# OPID_351_5V_Step-down_regulator_v2.net
KiCad netlist of a schematic drawn in Altium Designer
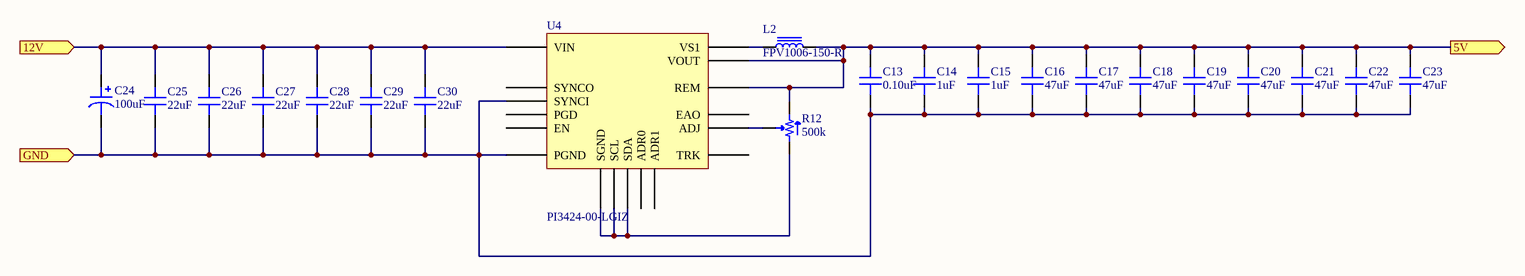
[diagram p0: OPID[351] 5V Step-down regulator v2.SchDoc]

(export (version "E")
  (design (tool "Eeschema 10.0.6"))
  (components
    (comp (ref "C13")
      (value "0.10uF")
      (footprint "CAP 1206/3216 - 1.0MM")
      (description "CAP CER 0.1UF 50V X7R 1206")
      (fields
        (field (name "PART NUMBER") "GRM319R71H104KA01D")
        (field (name "MANUFACTURER") "Murata Electronics North America")
      )
      (libsource (lib "Celestial Library Database") (part "Capacitor"))
    )
    (comp (ref "C14")
      (value "1uF")
      (footprint "CAP 0603/1608")
      (description "CAP CER 1UF 16V X7R 0603")
      (fields
        (field (name "PART NUMBER") "GRM188R71C105KA12D")
        (field (name "MANUFACTURER") "Murata Electronics North America")
      )
      (libsource (lib "Celestial Library Database") (part "Capacitor"))
    )
    (comp (ref "C15")
      (value "1uF")
      (footprint "CAP 0603/1608")
      (description "CAP CER 1UF 16V X7R 0603")
      (fields
        (field (name "PART NUMBER") "GRM188R71C105KA12D")
        (field (name "MANUFACTURER") "Murata Electronics North America")
      )
      (libsource (lib "Celestial Library Database") (part "Capacitor"))
    )
    (comp (ref "C16")
      (value "47uF")
      (footprint "CAP 1206/3216")
      (description "CAP CER 47UF 10V X5R 1206")
      (fields
        (field (name "PART NUMBER") "GRM31CR61A476ME15L")
        (field (name "MANUFACTURER") "Murata Electronics North America")
      )
      (libsource (lib "Celestial Library Database") (part "Capacitor"))
    )
    (comp (ref "C17")
      (value "47uF")
      (footprint "CAP 1206/3216")
      (description "CAP CER 47UF 10V X5R 1206")
      (fields
        (field (name "PART NUMBER") "GRM31CR61A476ME15L")
        (field (name "MANUFACTURER") "Murata Electronics North America")
      )
      (libsource (lib "Celestial Library Database") (part "Capacitor"))
    )
    (comp (ref "C18")
      (value "47uF")
      (footprint "CAP 1206/3216")
      (description "CAP CER 47UF 10V X5R 1206")
      (fields
        (field (name "PART NUMBER") "GRM31CR61A476ME15L")
        (field (name "MANUFACTURER") "Murata Electronics North America")
      )
      (libsource (lib "Celestial Library Database") (part "Capacitor"))
    )
    (comp (ref "C19")
      (value "47uF")
      (footprint "CAP 1206/3216")
      (description "CAP CER 47UF 10V X5R 1206")
      (fields
        (field (name "PART NUMBER") "GRM31CR61A476ME15L")
        (field (name "MANUFACTURER") "Murata Electronics North America")
      )
      (libsource (lib "Celestial Library Database") (part "Capacitor"))
    )
    (comp (ref "C20")
      (value "47uF")
      (footprint "CAP 1206/3216")
      (description "CAP CER 47UF 10V X5R 1206")
      (fields
        (field (name "PART NUMBER") "GRM31CR61A476ME15L")
        (field (name "MANUFACTURER") "Murata Electronics North America")
      )
      (libsource (lib "Celestial Library Database") (part "Capacitor"))
    )
    (comp (ref "C21")
      (value "47uF")
      (footprint "CAP 1206/3216")
      (description "CAP CER 47UF 10V X5R 1206")
      (fields
        (field (name "PART NUMBER") "GRM31CR61A476ME15L")
        (field (name "MANUFACTURER") "Murata Electronics North America")
      )
      (libsource (lib "Celestial Library Database") (part "Capacitor"))
    )
    (comp (ref "C22")
      (value "47uF")
      (footprint "CAP 1206/3216")
      (description "CAP CER 47UF 10V X5R 1206")
      (fields
        (field (name "PART NUMBER") "GRM31CR61A476ME15L")
        (field (name "MANUFACTURER") "Murata Electronics North America")
      )
      (libsource (lib "Celestial Library Database") (part "Capacitor"))
    )
    (comp (ref "C23")
      (value "47uF")
      (footprint "CAP 1206/3216")
      (description "CAP CER 47UF 10V X5R 1206")
      (fields
        (field (name "PART NUMBER") "GRM31CR61A476ME15L")
        (field (name "MANUFACTURER") "Murata Electronics North America")
      )
      (libsource (lib "Celestial Library Database") (part "Capacitor"))
    )
    (comp (ref "C24")
      (value "100uF")
      (footprint "CAP ALUM 10.3MM")
      (description "CAP ALUM 100UF 20% 50V SMD")
      (fields (field (name "PART NUMBER") "UUX1H101MNL1GS") (field (name "MANUFACTURER") "Nichicon"))
      (libsource (lib "Celestial Library Database") (part "Polarised Capacitor"))
    )
    (comp (ref "C25")
      (value "22uF")
      (footprint "CAP 1206/3216")
      (description "CAP CER 22UF 25V X5R 1206")
      (fields
        (field (name "PART NUMBER") "GRM31CR61E226KE15L")
        (field (name "MANUFACTURER") "Murata Electronics North America")
      )
      (libsource (lib "Celestial Library Database") (part "Capacitor"))
    )
    (comp (ref "C26")
      (value "22uF")
      (footprint "CAP 1206/3216")
      (description "CAP CER 22UF 25V X5R 1206")
      (fields
        (field (name "PART NUMBER") "GRM31CR61E226KE15L")
        (field (name "MANUFACTURER") "Murata Electronics North America")
      )
      (libsource (lib "Celestial Library Database") (part "Capacitor"))
    )
    (comp (ref "C27")
      (value "22uF")
      (footprint "CAP 1206/3216")
      (description "CAP CER 22UF 25V X5R 1206")
      (fields
        (field (name "PART NUMBER") "GRM31CR61E226KE15L")
        (field (name "MANUFACTURER") "Murata Electronics North America")
      )
      (libsource (lib "Celestial Library Database") (part "Capacitor"))
    )
    (comp (ref "C28")
      (value "22uF")
      (footprint "CAP 1206/3216")
      (description "CAP CER 22UF 25V X5R 1206")
      (fields
        (field (name "PART NUMBER") "GRM31CR61E226KE15L")
        (field (name "MANUFACTURER") "Murata Electronics North America")
      )
      (libsource (lib "Celestial Library Database") (part "Capacitor"))
    )
    (comp (ref "C29")
      (value "22uF")
      (footprint "CAP 1206/3216")
      (description "CAP CER 22UF 25V X5R 1206")
      (fields
        (field (name "PART NUMBER") "GRM31CR61E226KE15L")
        (field (name "MANUFACTURER") "Murata Electronics North America")
      )
      (libsource (lib "Celestial Library Database") (part "Capacitor"))
    )
    (comp (ref "C30")
      (value "22uF")
      (footprint "CAP 1206/3216")
      (description "CAP CER 22UF 25V X5R 1206")
      (fields
        (field (name "PART NUMBER") "GRM31CR61E226KE15L")
        (field (name "MANUFACTURER") "Murata Electronics North America")
      )
      (libsource (lib "Celestial Library Database") (part "Capacitor"))
    )
    (comp (ref "L2")
      (value "FPV1006-150-R")
      (footprint "FPV1006-150-R")
      (description "FIXED IND 150NH 25A 0.41 MOHM")
      (libsource (lib "Vortex-component-database") (part "FPV1006-150-R"))
    )
    (comp (ref "R12")
      (value "500k")
      (footprint "POT Panasonic EVM")
      (description "TRIMMER 500K OHM 0.15W SMD")
      (fields
        (field (name "PART NUMBER") "EVM-3YSX50B55")
        (field (name "MANUFACTURER") "Panasonic Electronic Components")
      )
      (libsource (lib "Celestial Library Database") (part "Potentiometer"))
    )
    (comp (ref "U4")
      (value "PI3424-00-LGIZ")
      (footprint "PI34xx-00")
      (libsource (lib "Vortex-component-database") (part "PI34xx-00"))
    )
  )
  (nets
    (net (code "1") (name "/5V") (class "Default")
      (node (ref "C13") (pin "2") (pinfunction "2_2") (pintype "passive"))
      (node (ref "C14") (pin "2") (pinfunction "2_2") (pintype "passive"))
      (node (ref "C15") (pin "2") (pinfunction "2_2") (pintype "passive"))
      (node (ref "C16") (pin "2") (pinfunction "2_2") (pintype "passive"))
      (node (ref "C17") (pin "2") (pinfunction "2_2") (pintype "passive"))
      (node (ref "C18") (pin "2") (pinfunction "2_2") (pintype "passive"))
      (node (ref "C19") (pin "2") (pinfunction "2_2") (pintype "passive"))
      (node (ref "C20") (pin "2") (pinfunction "2_2") (pintype "passive"))
      (node (ref "C21") (pin "2") (pinfunction "2_2") (pintype "passive"))
      (node (ref "C22") (pin "2") (pinfunction "2_2") (pintype "passive"))
      (node (ref "C23") (pin "2") (pinfunction "2_2") (pintype "passive"))
      (node (ref "L2") (pin "2") (pinfunction "2_2") (pintype "passive"))
      (node (ref "R12") (pin "3") (pinfunction "3_3") (pintype "passive"))
      (node (ref "U4") (pin "REM") (pinfunction "REM_REM") (pintype "passive"))
      (node (ref "U4") (pin "VOUT") (pinfunction "VOUT_VOUT") (pintype "passive"))
    )
    (net (code "2") (name "/12V") (class "Default")
      (node (ref "C24") (pin "1") (pinfunction "1_1") (pintype "passive"))
      (node (ref "C25") (pin "2") (pinfunction "2_2") (pintype "passive"))
      (node (ref "C26") (pin "2") (pinfunction "2_2") (pintype "passive"))
      (node (ref "C27") (pin "2") (pinfunction "2_2") (pintype "passive"))
      (node (ref "C28") (pin "2") (pinfunction "2_2") (pintype "passive"))
      (node (ref "C29") (pin "2") (pinfunction "2_2") (pintype "passive"))
      (node (ref "C30") (pin "2") (pinfunction "2_2") (pintype "passive"))
      (node (ref "U4") (pin "VIN") (pinfunction "VIN_VIN") (pintype "passive"))
    )
    (net (code "3") (name "/GND") (class "Default")
      (node (ref "C13") (pin "1") (pinfunction "1_1") (pintype "passive"))
      (node (ref "C14") (pin "1") (pinfunction "1_1") (pintype "passive"))
      (node (ref "C15") (pin "1") (pinfunction "1_1") (pintype "passive"))
      (node (ref "C16") (pin "1") (pinfunction "1_1") (pintype "passive"))
      (node (ref "C17") (pin "1") (pinfunction "1_1") (pintype "passive"))
      (node (ref "C18") (pin "1") (pinfunction "1_1") (pintype "passive"))
      (node (ref "C19") (pin "1") (pinfunction "1_1") (pintype "passive"))
      (node (ref "C20") (pin "1") (pinfunction "1_1") (pintype "passive"))
      (node (ref "C21") (pin "1") (pinfunction "1_1") (pintype "passive"))
      (node (ref "C22") (pin "1") (pinfunction "1_1") (pintype "passive"))
      (node (ref "C23") (pin "1") (pinfunction "1_1") (pintype "passive"))
      (node (ref "C24") (pin "2") (pinfunction "2_2") (pintype "passive"))
      (node (ref "C25") (pin "1") (pinfunction "1_1") (pintype "passive"))
      (node (ref "C26") (pin "1") (pinfunction "1_1") (pintype "passive"))
      (node (ref "C27") (pin "1") (pinfunction "1_1") (pintype "passive"))
      (node (ref "C28") (pin "1") (pinfunction "1_1") (pintype "passive"))
      (node (ref "C29") (pin "1") (pinfunction "1_1") (pintype "passive"))
      (node (ref "C30") (pin "1") (pinfunction "1_1") (pintype "passive"))
      (node (ref "U4") (pin "PGND") (pinfunction "PGND_PGND") (pintype "passive"))
      (node (ref "U4") (pin "SYNCI") (pinfunction "SYNCI_SYNCI") (pintype "passive"))
    )
    (net (code "4") (name "Net-(L2-Pad1)") (class "Default")
      (node (ref "L2") (pin "1") (pinfunction "1_1") (pintype "passive"))
      (node (ref "U4") (pin "VS1") (pinfunction "VS1_VS1") (pintype "passive"))
    )
    (net (code "5") (name "Net-(R12-Pad1)") (class "Default")
      (node (ref "R12") (pin "1") (pinfunction "1_1") (pintype "passive"))
      (node (ref "U4") (pin "SCL") (pinfunction "SCL_SCL") (pintype "passive"))
      (node (ref "U4") (pin "SDA") (pinfunction "SDA_SDA") (pintype "passive"))
      (node (ref "U4") (pin "SGND") (pinfunction "SGND_SGND") (pintype "passive"))
    )
    (net (code "6") (name "Net-(R12-Pad2)") (class "Default")
      (node (ref "R12") (pin "2") (pinfunction "2_2") (pintype "passive"))
      (node (ref "U4") (pin "ADJ") (pinfunction "ADJ_ADJ") (pintype "passive"))
    )
    (net (code "7") (name "unconnected-(U4-PadADR0)") (class "Default")
      (node (ref "U4") (pin "ADR0") (pinfunction "ADR0_ADR0") (pintype "passive"))
    )
    (net (code "8") (name "unconnected-(U4-PadADR1)") (class "Default")
      (node (ref "U4") (pin "ADR1") (pinfunction "ADR1_ADR1") (pintype "passive"))
    )
    (net (code "9") (name "unconnected-(U4-PadEAO)") (class "Default")
      (node (ref "U4") (pin "EAO") (pinfunction "EAO_EAO") (pintype "passive"))
    )
    (net (code "10") (name "unconnected-(U4-PadEN)") (class "Default")
      (node (ref "U4") (pin "EN") (pinfunction "EN_EN") (pintype "passive"))
    )
    (net (code "11") (name "unconnected-(U4-PadPGD)") (class "Default")
      (node (ref "U4") (pin "PGD") (pinfunction "PGD_PGD") (pintype "passive"))
    )
    (net (code "12") (name "unconnected-(U4-PadSYNCO)") (class "Default")
      (node (ref "U4") (pin "SYNCO") (pinfunction "SYNCO_SYNCO") (pintype "passive"))
    )
    (net (code "13") (name "unconnected-(U4-PadTRK)") (class "Default")
      (node (ref "U4") (pin "TRK") (pinfunction "TRK_TRK") (pintype "passive"))
    )
  )
)
